# current_sense_INA260.net
KiCad netlist of a schematic drawn in EAGLE
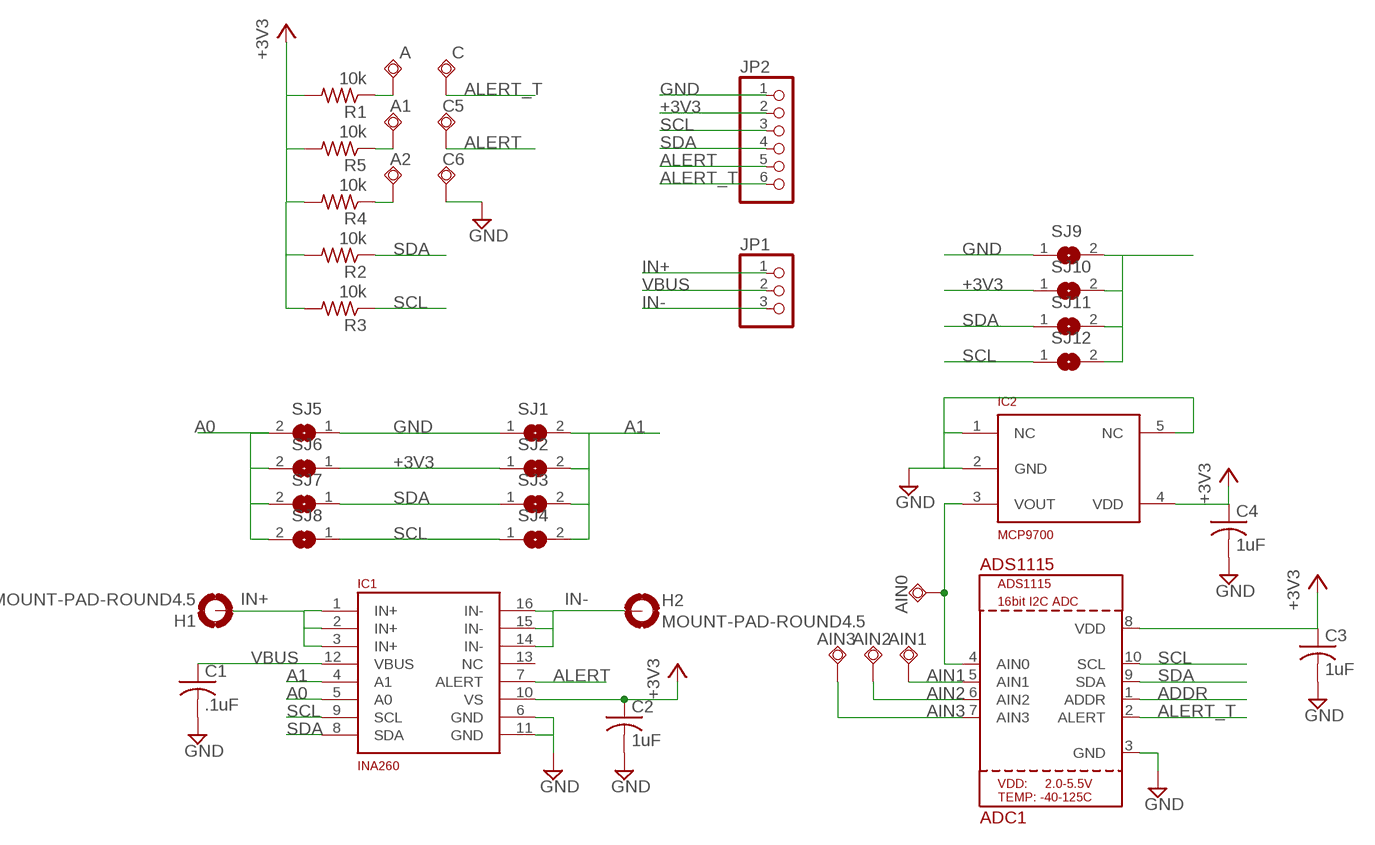
[diagram p0: schematic, sheet 1]

(export (version "E")
  (design (tool "Eeschema 10.0.6"))
  (components
    (comp (ref "A")
      (value "TPSQTP20SQ")
      (footprint "eagle-import:TP20SQ")
      (libsource (lib "eagle-import") (part "TPSQTP20SQ"))
    )
    (comp (ref "A1")
      (value "TPSQTP20SQ")
      (footprint "eagle-import:TP20SQ")
      (libsource (lib "eagle-import") (part "TPSQTP20SQ"))
    )
    (comp (ref "A2")
      (value "TPSQTP20SQ")
      (footprint "eagle-import:TP20SQ")
      (libsource (lib "eagle-import") (part "TPSQTP20SQ"))
    )
    (comp (ref "ADC1")
      (value "ADS1115")
      (footprint "eagle-import:MSOP10")
      (libsource (lib "eagle-import") (part "ADS1115"))
    )
    (comp (ref "AIN0")
      (value "TPSQTP20SQ")
      (footprint "eagle-import:TP20SQ")
      (libsource (lib "eagle-import") (part "TPSQTP20SQ"))
    )
    (comp (ref "AIN1")
      (value "TPSQTP20SQ")
      (footprint "eagle-import:TP20SQ")
      (libsource (lib "eagle-import") (part "TPSQTP20SQ"))
    )
    (comp (ref "AIN2")
      (value "TPSQTP20SQ")
      (footprint "eagle-import:TP20SQ")
      (libsource (lib "eagle-import") (part "TPSQTP20SQ"))
    )
    (comp (ref "AIN3")
      (value "TPSQTP20SQ")
      (footprint "eagle-import:TP20SQ")
      (libsource (lib "eagle-import") (part "TPSQTP20SQ"))
    )
    (comp (ref "C")
      (value "C")
      (footprint "eagle-import:TP20SQ")
      (libsource (lib "eagle-import") (part "TPSQTP20SQ"))
    )
    (comp (ref "C1")
      (value ".1uF")
      (footprint "eagle-import:C0805K")
      (libsource (lib "eagle-import") (part "C-USC0805K"))
    )
    (comp (ref "C2")
      (value "1uF")
      (footprint "eagle-import:C0805K")
      (libsource (lib "eagle-import") (part "C-USC0805K"))
    )
    (comp (ref "C3")
      (value "1uF")
      (footprint "eagle-import:C0805K")
      (libsource (lib "eagle-import") (part "C-USC0805K"))
    )
    (comp (ref "C4")
      (value "1uF")
      (footprint "eagle-import:C0805K")
      (libsource (lib "eagle-import") (part "C-USC0805K"))
    )
    (comp (ref "C5")
      (value "TPSQTP20SQ")
      (footprint "eagle-import:TP20SQ")
      (libsource (lib "eagle-import") (part "TPSQTP20SQ"))
    )
    (comp (ref "C6")
      (value "TPSQTP20SQ")
      (footprint "eagle-import:TP20SQ")
      (libsource (lib "eagle-import") (part "TPSQTP20SQ"))
    )
    (comp (ref "H1")
      (value "MOUNT-PAD-ROUND4.5")
      (footprint "eagle-import:4,5-PAD")
      (libsource (lib "eagle-import") (part "MOUNT-PAD-ROUND4.5"))
    )
    (comp (ref "H2")
      (value "MOUNT-PAD-ROUND4.5")
      (footprint "eagle-import:4,5-PAD")
      (libsource (lib "eagle-import") (part "MOUNT-PAD-ROUND4.5"))
    )
    (comp (ref "IC1")
      (value "INA260")
      (footprint "eagle-import:TSSOP16")
      (libsource (lib "eagle-import") (part "INA260"))
    )
    (comp (ref "IC2")
      (value "MCP9700")
      (footprint "eagle-import:SC70")
      (libsource (lib "eagle-import") (part "MCP9700"))
    )
    (comp (ref "JP1")
      (value "PINHD-1X3")
      (footprint "eagle-import:1X03")
      (libsource (lib "eagle-import") (part "PINHD-1X3"))
    )
    (comp (ref "JP2")
      (value "PINHD-1X6")
      (footprint "eagle-import:1X06")
      (libsource (lib "eagle-import") (part "PINHD-1X6"))
    )
    (comp (ref "R1")
      (value "10k")
      (footprint "eagle-import:R0805")
      (libsource (lib "eagle-import") (part "R-US_R0805"))
    )
    (comp (ref "R2")
      (value "10k")
      (footprint "eagle-import:R0805")
      (libsource (lib "eagle-import") (part "R-US_R0805"))
    )
    (comp (ref "R3")
      (value "10k")
      (footprint "eagle-import:R0805")
      (libsource (lib "eagle-import") (part "R-US_R0805"))
    )
    (comp (ref "R4")
      (value "10k")
      (footprint "eagle-import:R0805")
      (libsource (lib "eagle-import") (part "R-US_R0805"))
    )
    (comp (ref "R5")
      (value "10k")
      (footprint "eagle-import:R0805")
      (libsource (lib "eagle-import") (part "R-US_R0805"))
    )
    (comp (ref "SJ1") (value "SJ") (footprint "eagle-import:SJ") (libsource (lib "eagle-import") (part "SJ")))
    (comp (ref "SJ2") (value "SJ") (footprint "eagle-import:SJ") (libsource (lib "eagle-import") (part "SJ")))
    (comp (ref "SJ3") (value "SJ") (footprint "eagle-import:SJ") (libsource (lib "eagle-import") (part "SJ")))
    (comp (ref "SJ4") (value "SJ") (footprint "eagle-import:SJ") (libsource (lib "eagle-import") (part "SJ")))
    (comp (ref "SJ5") (value "SJ") (footprint "eagle-import:SJ") (libsource (lib "eagle-import") (part "SJ")))
    (comp (ref "SJ6") (value "SJ") (footprint "eagle-import:SJ") (libsource (lib "eagle-import") (part "SJ")))
    (comp (ref "SJ7") (value "SJ") (footprint "eagle-import:SJ") (libsource (lib "eagle-import") (part "SJ")))
    (comp (ref "SJ8") (value "SJ") (footprint "eagle-import:SJ") (libsource (lib "eagle-import") (part "SJ")))
    (comp (ref "SJ9") (value "SJ") (footprint "eagle-import:SJ") (libsource (lib "eagle-import") (part "SJ")))
    (comp (ref "SJ10")
      (value "SJ")
      (footprint "eagle-import:SJ")
      (libsource (lib "eagle-import") (part "SJ"))
    )
    (comp (ref "SJ11")
      (value "SJ")
      (footprint "eagle-import:SJ")
      (libsource (lib "eagle-import") (part "SJ"))
    )
    (comp (ref "SJ12")
      (value "SJ")
      (footprint "eagle-import:SJ")
      (libsource (lib "eagle-import") (part "SJ"))
    )
  )
  (nets
    (net (code "1") (name "+3V3") (class "Default")
      (node (ref "ADC1") (pin "8") (pinfunction "VDD_8") (pintype "bidirectional"))
      (node (ref "C2") (pin "1") (pinfunction "1_1") (pintype "passive"))
      (node (ref "C3") (pin "1") (pinfunction "1_1") (pintype "passive"))
      (node (ref "C4") (pin "1") (pinfunction "1_1") (pintype "passive"))
      (node (ref "IC1") (pin "10") (pinfunction "VS_10") (pintype "bidirectional"))
      (node (ref "IC2") (pin "4") (pinfunction "VDD_4") (pintype "bidirectional"))
      (node (ref "JP2") (pin "2") (pinfunction "2_2") (pintype "passive"))
      (node (ref "R1") (pin "2") (pinfunction "2_2") (pintype "passive"))
      (node (ref "R2") (pin "2") (pinfunction "2_2") (pintype "passive"))
      (node (ref "R3") (pin "2") (pinfunction "2_2") (pintype "passive"))
      (node (ref "R4") (pin "2") (pinfunction "2_2") (pintype "passive"))
      (node (ref "R5") (pin "2") (pinfunction "2_2") (pintype "passive"))
      (node (ref "SJ10") (pin "1") (pinfunction "1_1") (pintype "passive"))
      (node (ref "SJ2") (pin "1") (pinfunction "1_1") (pintype "passive"))
      (node (ref "SJ6") (pin "1") (pinfunction "1_1") (pintype "passive"))
    )
    (net (code "2") (name "/A0") (class "Default")
      (node (ref "IC1") (pin "5") (pinfunction "A0_5") (pintype "bidirectional"))
      (node (ref "SJ5") (pin "2") (pinfunction "2_2") (pintype "passive"))
      (node (ref "SJ6") (pin "2") (pinfunction "2_2") (pintype "passive"))
      (node (ref "SJ7") (pin "2") (pinfunction "2_2") (pintype "passive"))
      (node (ref "SJ8") (pin "2") (pinfunction "2_2") (pintype "passive"))
    )
    (net (code "3") (name "/A1") (class "Default")
      (node (ref "IC1") (pin "4") (pinfunction "A1_4") (pintype "bidirectional"))
      (node (ref "SJ1") (pin "2") (pinfunction "2_2") (pintype "passive"))
      (node (ref "SJ2") (pin "2") (pinfunction "2_2") (pintype "passive"))
      (node (ref "SJ3") (pin "2") (pinfunction "2_2") (pintype "passive"))
      (node (ref "SJ4") (pin "2") (pinfunction "2_2") (pintype "passive"))
    )
    (net (code "4") (name "/ADDR") (class "Default")
      (node (ref "ADC1") (pin "1") (pinfunction "ADDR_1") (pintype "bidirectional"))
      (node (ref "SJ10") (pin "2") (pinfunction "2_2") (pintype "passive"))
      (node (ref "SJ11") (pin "2") (pinfunction "2_2") (pintype "passive"))
      (node (ref "SJ12") (pin "2") (pinfunction "2_2") (pintype "passive"))
      (node (ref "SJ9") (pin "2") (pinfunction "2_2") (pintype "passive"))
    )
    (net (code "5") (name "/AIN1") (class "Default")
      (node (ref "ADC1") (pin "5") (pinfunction "AIN1_5") (pintype "bidirectional"))
      (node (ref "AIN1") (pin "TP") (pinfunction "TP_TP") (pintype "input"))
    )
    (net (code "6") (name "/AIN2") (class "Default")
      (node (ref "ADC1") (pin "6") (pinfunction "AIN2_6") (pintype "bidirectional"))
      (node (ref "AIN2") (pin "TP") (pinfunction "TP_TP") (pintype "input"))
    )
    (net (code "7") (name "/AIN3") (class "Default")
      (node (ref "ADC1") (pin "7") (pinfunction "AIN3_7") (pintype "bidirectional"))
      (node (ref "AIN3") (pin "TP") (pinfunction "TP_TP") (pintype "input"))
    )
    (net (code "8") (name "/ALERT") (class "Default")
      (node (ref "C5") (pin "TP") (pinfunction "TP_TP") (pintype "input"))
      (node (ref "IC1") (pin "7") (pinfunction "ALERT_7") (pintype "bidirectional"))
      (node (ref "JP2") (pin "5") (pinfunction "5_5") (pintype "passive"))
    )
    (net (code "9") (name "/ALERT_T") (class "Default")
      (node (ref "ADC1") (pin "2") (pinfunction "ALERT_2") (pintype "bidirectional"))
      (node (ref "C") (pin "TP") (pinfunction "TP_TP") (pintype "input"))
      (node (ref "JP2") (pin "6") (pinfunction "6_6") (pintype "passive"))
    )
    (net (code "10") (name "/IN+") (class "Default")
      (node (ref "H1") (pin "B4,5") (pinfunction "MOUNT_B4,5") (pintype "passive"))
      (node (ref "IC1") (pin "1") (pinfunction "IN+_1") (pintype "bidirectional"))
      (node (ref "IC1") (pin "2") (pinfunction "IN+_2") (pintype "bidirectional"))
      (node (ref "IC1") (pin "3") (pinfunction "IN+_3") (pintype "bidirectional"))
      (node (ref "JP1") (pin "1") (pinfunction "1_1") (pintype "passive"))
    )
    (net (code "11") (name "/IN-") (class "Default")
      (node (ref "H2") (pin "B4,5") (pinfunction "MOUNT_B4,5") (pintype "passive"))
      (node (ref "IC1") (pin "14") (pinfunction "IN-_14") (pintype "bidirectional"))
      (node (ref "IC1") (pin "15") (pinfunction "IN-_15") (pintype "bidirectional"))
      (node (ref "IC1") (pin "16") (pinfunction "IN-_16") (pintype "bidirectional"))
      (node (ref "JP1") (pin "3") (pinfunction "3_3") (pintype "passive"))
    )
    (net (code "12") (name "/SCL") (class "Default")
      (node (ref "ADC1") (pin "10") (pinfunction "SCL_10") (pintype "bidirectional"))
      (node (ref "IC1") (pin "9") (pinfunction "SCL_9") (pintype "bidirectional"))
      (node (ref "JP2") (pin "3") (pinfunction "3_3") (pintype "passive"))
      (node (ref "R3") (pin "1") (pinfunction "1_1") (pintype "passive"))
      (node (ref "SJ12") (pin "1") (pinfunction "1_1") (pintype "passive"))
      (node (ref "SJ4") (pin "1") (pinfunction "1_1") (pintype "passive"))
      (node (ref "SJ8") (pin "1") (pinfunction "1_1") (pintype "passive"))
    )
    (net (code "13") (name "/SDA") (class "Default")
      (node (ref "ADC1") (pin "9") (pinfunction "SDA_9") (pintype "bidirectional"))
      (node (ref "IC1") (pin "8") (pinfunction "SDA_8") (pintype "bidirectional"))
      (node (ref "JP2") (pin "4") (pinfunction "4_4") (pintype "passive"))
      (node (ref "R2") (pin "1") (pinfunction "1_1") (pintype "passive"))
      (node (ref "SJ11") (pin "1") (pinfunction "1_1") (pintype "passive"))
      (node (ref "SJ3") (pin "1") (pinfunction "1_1") (pintype "passive"))
      (node (ref "SJ7") (pin "1") (pinfunction "1_1") (pintype "passive"))
    )
    (net (code "14") (name "/VBUS") (class "Default")
      (node (ref "C1") (pin "1") (pinfunction "1_1") (pintype "passive"))
      (node (ref "IC1") (pin "12") (pinfunction "VBUS_12") (pintype "bidirectional"))
      (node (ref "JP1") (pin "2") (pinfunction "2_2") (pintype "passive"))
    )
    (net (code "15") (name "GND") (class "Default")
      (node (ref "ADC1") (pin "3") (pinfunction "GND_3") (pintype "bidirectional"))
      (node (ref "C1") (pin "2") (pinfunction "2_2") (pintype "passive"))
      (node (ref "C2") (pin "2") (pinfunction "2_2") (pintype "passive"))
      (node (ref "C3") (pin "2") (pinfunction "2_2") (pintype "passive"))
      (node (ref "C4") (pin "2") (pinfunction "2_2") (pintype "passive"))
      (node (ref "C6") (pin "TP") (pinfunction "TP_TP") (pintype "input"))
      (node (ref "IC1") (pin "11") (pinfunction "GND_11") (pintype "bidirectional"))
      (node (ref "IC1") (pin "6") (pinfunction "GND_6") (pintype "bidirectional"))
      (node (ref "IC2") (pin "1") (pinfunction "NC_1") (pintype "bidirectional"))
      (node (ref "IC2") (pin "2") (pinfunction "GND_2") (pintype "bidirectional"))
      (node (ref "IC2") (pin "5") (pinfunction "NC_5") (pintype "bidirectional"))
      (node (ref "JP2") (pin "1") (pinfunction "1_1") (pintype "passive"))
      (node (ref "SJ1") (pin "1") (pinfunction "1_1") (pintype "passive"))
      (node (ref "SJ5") (pin "1") (pinfunction "1_1") (pintype "passive"))
      (node (ref "SJ9") (pin "1") (pinfunction "1_1") (pintype "passive"))
    )
    (net (code "16") (name "Net-(A-PadTP)") (class "Default")
      (node (ref "A") (pin "TP") (pinfunction "TP_TP") (pintype "input"))
      (node (ref "R1") (pin "1") (pinfunction "1_1") (pintype "passive"))
    )
    (net (code "17") (name "Net-(A1-PadTP)") (class "Default")
      (node (ref "A1") (pin "TP") (pinfunction "TP_TP") (pintype "input"))
      (node (ref "R5") (pin "1") (pinfunction "1_1") (pintype "passive"))
    )
    (net (code "18") (name "Net-(A2-PadTP)") (class "Default")
      (node (ref "A2") (pin "TP") (pinfunction "TP_TP") (pintype "input"))
      (node (ref "R4") (pin "1") (pinfunction "1_1") (pintype "passive"))
    )
    (net (code "19") (name "Net-(ADC1-AIN0)") (class "Default")
      (node (ref "ADC1") (pin "4") (pinfunction "AIN0_4") (pintype "bidirectional"))
      (node (ref "AIN0") (pin "TP") (pinfunction "TP_TP") (pintype "input"))
      (node (ref "IC2") (pin "3") (pinfunction "VOUT_3") (pintype "bidirectional"))
    )
    (net (code "20") (name "unconnected-(IC1-NC-Pad13)") (class "Default")
      (node (ref "IC1") (pin "13") (pinfunction "NC_13") (pintype "bidirectional"))
    )
  )
)
